# Power.net
KiCad netlist of a schematic drawn in Altium Designer
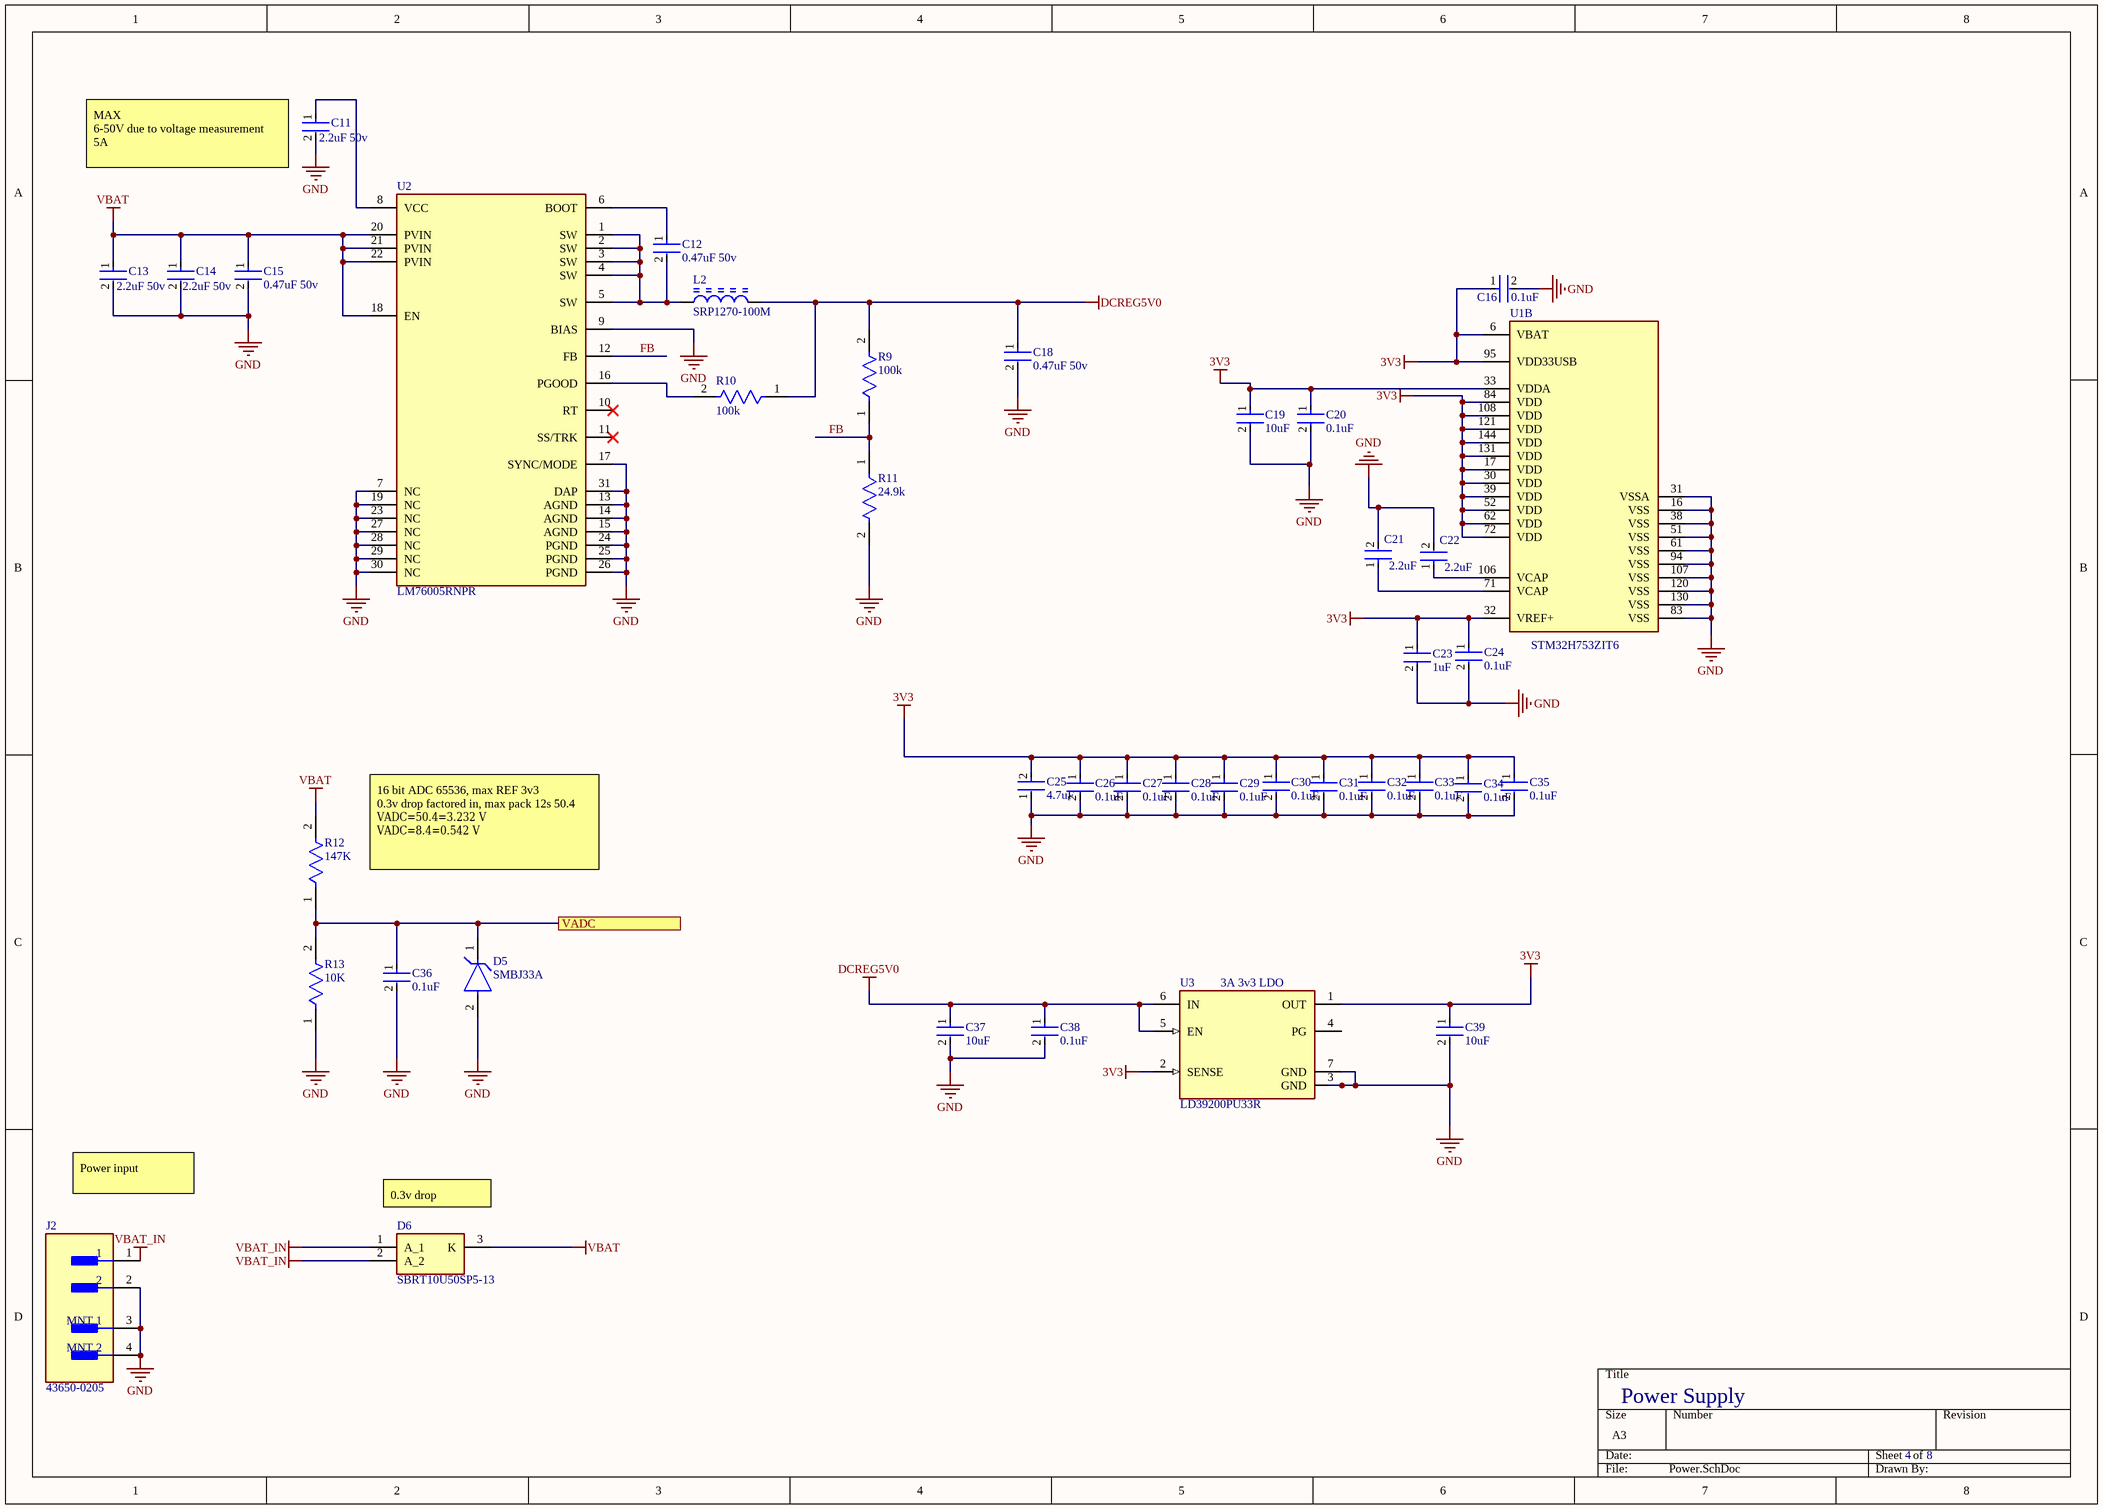
[diagram p0:  Power.SchDoc]

(export (version "E")
  (design (tool "Eeschema 10.0.6"))
  (components
    (comp (ref "C11")
      (value "2.2uF 50v")
      (footprint "FP-GRM188-0_2-IPC_C")
      (libsource (lib "Altium Content Vault") (part "11868f565c42a9108669ba33697ecf6"))
    )
    (comp (ref "C12")
      (value "0.47uF 50v")
      (footprint "FP-0603-L_1_6_0_15-W_0_8-MFG")
      (description "UMK107ABJ474KA-T")
      (fields (field (name "TOLERANCE") "10%") (field (name "VOLTAGE") "50V"))
      (libsource (lib "Altium Content Vault") (part "11868f565c42a9108669ba33697ecf6"))
    )
    (comp (ref "C13")
      (value "2.2uF 50v")
      (footprint "FP-GRM188-0_2-IPC_C")
      (libsource (lib "Altium Content Vault") (part "11868f565c42a9108669ba33697ecf6"))
    )
    (comp (ref "C14")
      (value "2.2uF 50v")
      (footprint "FP-GRM188-0_2-IPC_C")
      (libsource (lib "Altium Content Vault") (part "11868f565c42a9108669ba33697ecf6"))
    )
    (comp (ref "C15")
      (value "0.47uF 50v")
      (footprint "FP-0603-L_1_6_0_15-W_0_8-MFG")
      (description "UMK107ABJ474KA-T")
      (fields (field (name "TOLERANCE") "10%") (field (name "VOLTAGE") "50V"))
      (libsource (lib "Altium Content Vault") (part "11868f565c42a9108669ba33697ecf6"))
    )
    (comp (ref "C16")
      (value "0.1uF")
      (footprint "FP-CL10-IPC_C")
      (description "Cap Ceramic 100nF 16V X7R ±10% Pad SMD 0603 +125°C T/R\r\nCL10B104KO8WPNC")
      (fields (field (name "TOLERANCE") "10%"))
      (libsource (lib "Altium Content Vault") (part "b4654b650e69147ec39a6b967a45e02"))
    )
    (comp (ref "C18")
      (value "0.47uF 50v")
      (footprint "FP-0603-L_1_6_0_15-W_0_8-MFG")
      (description "UMK107ABJ474KA-T")
      (fields (field (name "TOLERANCE") "10%") (field (name "VOLTAGE") "50V"))
      (libsource (lib "Altium Content Vault") (part "11868f565c42a9108669ba33697ecf6"))
    )
    (comp (ref "C19")
      (value "10uF")
      (footprint "FP-CL10-IPC_C")
      (description "Cap Ceramic 10uF 16V X6S ±20% Pad SMD 0603 +105°C T/R\r\nCL10X106MO8NRNC")
      (fields (field (name "TOLERANCE") "20%"))
      (libsource (lib "Altium Content Vault") (part "b4654b650e69147ec39a6b967a45e02"))
    )
    (comp (ref "C20")
      (value "0.1uF")
      (footprint "FP-CL10-IPC_C")
      (description "Cap Ceramic 100nF 16V X7R ±10% Pad SMD 0603 +125°C T/R\r\nCL10B104KO8WPNC")
      (fields (field (name "TOLERANCE") "10%"))
      (libsource (lib "Altium Content Vault") (part "b4654b650e69147ec39a6b967a45e02"))
    )
    (comp (ref "C21")
      (value "2.2uF")
      (footprint "FP-CL10-IPC_C")
      (description "Cap Ceramic 2.2uF 16V X5R ±10% Pad SMD 0603 +85°C T/R\r\nCL10A225KO8NNND")
      (fields (field (name "TOLERANCE") "10%"))
      (libsource (lib "Altium Content Vault") (part "b4654b650e69147ec39a6b967a45e02"))
    )
    (comp (ref "C22")
      (value "2.2uF")
      (footprint "FP-CL10-IPC_C")
      (description "Cap Ceramic 2.2uF 16V X5R ±10% Pad SMD 0603 +85°C T/R\r\nCL10A225KO8NNND")
      (fields (field (name "TOLERANCE") "10%"))
      (libsource (lib "Altium Content Vault") (part "b4654b650e69147ec39a6b967a45e02"))
    )
    (comp (ref "C23")
      (value "1uF")
      (footprint "FP-CL10-IPC_C")
      (description "Cap Ceramic 1uF 16V X7R ±10% Pad SMD 0603 +125°C T/R\r\nCL10B105KO8NNNL")
      (fields (field (name "TOLERANCE") "10%"))
      (libsource (lib "Altium Content Vault") (part "b4654b650e69147ec39a6b967a45e02"))
    )
    (comp (ref "C24")
      (value "0.1uF")
      (footprint "FP-CL10-IPC_C")
      (description "Cap Ceramic 100nF 16V X7R ±10% Pad SMD 0603 +125°C T/R\r\nCL10B104KO8WPNC")
      (fields (field (name "TOLERANCE") "10%"))
      (libsource (lib "Altium Content Vault") (part "b4654b650e69147ec39a6b967a45e02"))
    )
    (comp (ref "C25")
      (value "4.7uF")
      (footprint "FP-C1608-080-0_1-MFG")
      (description "Multilayer Ceramic Capacitors 4.7μF ±10% 25V X5R SMD 0603\r\nC1608X5R1E475K080AC")
      (fields (field (name "TOLERANCE") "10%"))
      (libsource (lib "Altium Content Vault") (part "236180d848d6139a670b325ea6854c9"))
    )
    (comp (ref "C26")
      (value "0.1uF")
      (footprint "FP-CL10-IPC_C")
      (description "Cap Ceramic 100nF 16V X7R ±10% Pad SMD 0603 +125°C T/R\r\nCL10B104KO8WPNC")
      (fields (field (name "TOLERANCE") "10%"))
      (libsource (lib "Altium Content Vault") (part "b4654b650e69147ec39a6b967a45e02"))
    )
    (comp (ref "C27")
      (value "0.1uF")
      (footprint "FP-CL10-IPC_C")
      (description "Cap Ceramic 100nF 16V X7R ±10% Pad SMD 0603 +125°C T/R\r\nCL10B104KO8WPNC")
      (fields (field (name "TOLERANCE") "10%"))
      (libsource (lib "Altium Content Vault") (part "b4654b650e69147ec39a6b967a45e02"))
    )
    (comp (ref "C28")
      (value "0.1uF")
      (footprint "FP-CL10-IPC_C")
      (description "Cap Ceramic 100nF 16V X7R ±10% Pad SMD 0603 +125°C T/R\r\nCL10B104KO8WPNC")
      (fields (field (name "TOLERANCE") "10%"))
      (libsource (lib "Altium Content Vault") (part "b4654b650e69147ec39a6b967a45e02"))
    )
    (comp (ref "C29")
      (value "0.1uF")
      (footprint "FP-CL10-IPC_C")
      (description "Cap Ceramic 100nF 16V X7R ±10% Pad SMD 0603 +125°C T/R\r\nCL10B104KO8WPNC")
      (fields (field (name "TOLERANCE") "10%"))
      (libsource (lib "Altium Content Vault") (part "b4654b650e69147ec39a6b967a45e02"))
    )
    (comp (ref "C30")
      (value "0.1uF")
      (footprint "FP-CL10-IPC_C")
      (description "Cap Ceramic 100nF 16V X7R ±10% Pad SMD 0603 +125°C T/R\r\nCL10B104KO8WPNC")
      (fields (field (name "TOLERANCE") "10%"))
      (libsource (lib "Altium Content Vault") (part "b4654b650e69147ec39a6b967a45e02"))
    )
    (comp (ref "C31")
      (value "0.1uF")
      (footprint "FP-CL10-IPC_C")
      (description "Cap Ceramic 100nF 16V X7R ±10% Pad SMD 0603 +125°C T/R\r\nCL10B104KO8WPNC")
      (fields (field (name "TOLERANCE") "10%"))
      (libsource (lib "Altium Content Vault") (part "b4654b650e69147ec39a6b967a45e02"))
    )
    (comp (ref "C32")
      (value "0.1uF")
      (footprint "FP-CL10-IPC_C")
      (description "Cap Ceramic 100nF 16V X7R ±10% Pad SMD 0603 +125°C T/R\r\nCL10B104KO8WPNC")
      (fields (field (name "TOLERANCE") "10%"))
      (libsource (lib "Altium Content Vault") (part "b4654b650e69147ec39a6b967a45e02"))
    )
    (comp (ref "C33")
      (value "0.1uF")
      (footprint "FP-CL10-IPC_C")
      (description "Cap Ceramic 100nF 16V X7R ±10% Pad SMD 0603 +125°C T/R\r\nCL10B104KO8WPNC")
      (fields (field (name "TOLERANCE") "10%"))
      (libsource (lib "Altium Content Vault") (part "b4654b650e69147ec39a6b967a45e02"))
    )
    (comp (ref "C34")
      (value "0.1uF")
      (footprint "FP-CL10-IPC_C")
      (description "Cap Ceramic 100nF 16V X7R ±10% Pad SMD 0603 +125°C T/R\r\nCL10B104KO8WPNC")
      (fields (field (name "TOLERANCE") "10%"))
      (libsource (lib "Altium Content Vault") (part "b4654b650e69147ec39a6b967a45e02"))
    )
    (comp (ref "C35")
      (value "0.1uF")
      (footprint "FP-CL10-IPC_C")
      (description "Cap Ceramic 100nF 16V X7R ±10% Pad SMD 0603 +125°C T/R\r\nCL10B104KO8WPNC")
      (fields (field (name "TOLERANCE") "10%"))
      (libsource (lib "Altium Content Vault") (part "b4654b650e69147ec39a6b967a45e02"))
    )
    (comp (ref "C36")
      (value "0.1uF")
      (footprint "FP-CL10-IPC_C")
      (description "Cap Ceramic 100nF 16V X7R ±10% Pad SMD 0603 +125°C T/R\r\nCL10B104KO8WPNC")
      (fields (field (name "TOLERANCE") "10%"))
      (libsource (lib "Altium Content Vault") (part "b4654b650e69147ec39a6b967a45e02"))
    )
    (comp (ref "C37")
      (value "10uF")
      (footprint "FP-CL10-IPC_C")
      (description "Cap Ceramic 10uF 16V X6S ±20% Pad SMD 0603 +105°C T/R\r\nCL10X106MO8NRNC")
      (fields (field (name "TOLERANCE") "20%"))
      (libsource (lib "Altium Content Vault") (part "b4654b650e69147ec39a6b967a45e02"))
    )
    (comp (ref "C38")
      (value "0.1uF")
      (footprint "FP-CL10-IPC_C")
      (description "Cap Ceramic 100nF 16V X7R ±10% Pad SMD 0603 +125°C T/R\r\nCL10B104KO8WPNC")
      (fields (field (name "TOLERANCE") "10%"))
      (libsource (lib "Altium Content Vault") (part "b4654b650e69147ec39a6b967a45e02"))
    )
    (comp (ref "C39")
      (value "10uF")
      (footprint "FP-CL10-IPC_C")
      (description "Cap Ceramic 10uF 16V X6S ±20% Pad SMD 0603 +105°C T/R\r\nCL10X106MO8NRNC")
      (fields (field (name "TOLERANCE") "20%"))
      (libsource (lib "Altium Content Vault") (part "b4654b650e69147ec39a6b967a45e02"))
    )
    (comp (ref "D5")
      (value "SMBJ33A")
      (footprint "FP-SMBJ-MFG")
      (description "TVS DIODE 33V 53.3V DO214AA")
      (fields
        (field (name "MANUFACTURER") "Littelfuse Inc")
        (field (name "OCTOPART") "https://octopart.com/smbj33a-littelfuse-350829")
      )
      (libsource (lib "Altium Content Vault") (part "f813f71cba58e380607f5dd3caf9714"))
    )
    (comp (ref "D6")
      (value "SBRT10U50SP5-13")
      (footprint "SamacSys:SBRT10U50SP513")
      (description "Diode")
      (fields (field (name "MOUSER PART NUMBER") "621-SBRT10U50SP5-13"))
      (libsource (lib "*") (part "SBRT10U50SP5-13"))
    )
    (comp (ref "J2")
      (value "43650-0205")
      (footprint "FP-43650-0205-MFG")
      (description "43650-0205 Conn Wire to Board HDR 2 POS 3mm Solder RA Side Entry Thru-Hole Micro-Fit 3.0™ Tray")
      (libsource (lib "Altium Content Vault") (part "56ec3178a87b3978bdc1b3682cd516a"))
    )
    (comp (ref "L2")
      (value "SRP1270-100M")
      (footprint "BOUR-SRP1270-100M-2_V")
      (description "Shielded Power Inductor, 10 uH, +/- 20%, 10 A, -55 to 125 degC, 2-Pin SMD, RoHS, Tape and Reel")
      (fields (field (name "TOLERANCE") "±20%") (field (name "MANUFACTURER") "Bourns"))
      (libsource (lib "Altium Content Vault") (part "BOUR-IND-2A"))
    )
    (comp (ref "R9")
      (value "100k")
      (footprint "FP-RC0603-0_55-IPC_C")
      (description "RC0603FR-07100KL RES SMD 100K OHM 1% 1/10W 0603")
      (fields (field (name "TOLERANCE") "1%"))
      (libsource (lib "Altium Content Vault") (part "1029c3af85768c4190bb7ad29bc67b5"))
    )
    (comp (ref "R10")
      (value "100k")
      (footprint "FP-RC0603-0_55-IPC_C")
      (description "RC0603FR-07100KL RES SMD 100K OHM 1% 1/10W 0603")
      (fields (field (name "TOLERANCE") "1%"))
      (libsource (lib "Altium Content Vault") (part "1029c3af85768c4190bb7ad29bc67b5"))
    )
    (comp (ref "R11")
      (value "24.9k")
      (footprint "FP-RG1608-IPC_C")
      (fields (field (name "TOLERANCE") "0.1%"))
      (libsource (lib "Altium Content Vault") (part "1029c3af85768c4190bb7ad29bc67b5"))
    )
    (comp (ref "R12")
      (value "147K")
      (footprint "FP-RT0603-MFG")
      (description "RT0603BRD07147KL\r\nRES SMD 147K OHM 0.1% 1/10W 0603")
      (fields (field (name "MANUFACTURER") "Yageo") (field (name "TOLERANCE") "0.001"))
      (libsource (lib "Altium Content Vault") (part "1029c3af85768c4190bb7ad29bc67b5"))
    )
    (comp (ref "R13")
      (value "10K")
      (footprint "FP-ERJPB3-IPC_C")
      (description "ERJ-PB3B1002V\r\nRES SMD 10K OHM 0.1% 1/5W 0603")
      (fields (field (name "TOLERANCE") "0.1%"))
      (libsource (lib "Altium Content Vault") (part "1029c3af85768c4190bb7ad29bc67b5"))
    )
    (comp (ref "U1")
      (value "STM32H753ZIT6")
      (footprint "FP-LQFP144-1A-MFG")
      (description "LQFP 144 20X20X1.4 2")
      (fields
        (field (name "MANUFACTURER") "STMicroelectronics")
        (field (name "OCTOPART") "https://octopart.com/stm32h753zit6-stmicroelectronics-87879771")
      )
      (libsource (lib "Altium Content Vault") (part "eeed45f8b0ec3d8db28e558541eef73"))
    )
    (comp (ref "U2")
      (value "LM76005RNPR")
      (footprint "FP-RNP0030A-MFG")
      (description "3.5-V TO 60-V, 5-A SYNCHRONOUS S")
      (libsource (lib "Altium Content Vault") (part "e2228dfeb00daf3b479f14d7f837c1f"))
    )
    (comp (ref "U3")
      (value "LD39200PU33R")
      (footprint "FP-DFN6-7946637-MFG")
      (description "IC REG LINEAR 3.3V 2A 6DFN")
      (libsource (lib "Altium Content Vault") (part "f0cfe00d12cb984572f50007c934a2d"))
    )
  )
  (nets
    (net (code "1") (name "/FB") (class "Default")
      (node (ref "R11") (pin "1") (pinfunction "1_1") (pintype "passive"))
      (node (ref "R9") (pin "1") (pinfunction "1_1") (pintype "passive"))
      (node (ref "U2") (pin "12") (pinfunction "FB_12") (pintype "passive"))
    )
    (net (code "2") (name "/VADC") (class "Default")
      (node (ref "C36") (pin "1") (pinfunction "1_1") (pintype "passive"))
      (node (ref "D5") (pin "1") (pinfunction "C_1") (pintype "passive"))
      (node (ref "R12") (pin "1") (pinfunction "1_1") (pintype "passive"))
      (node (ref "R13") (pin "2") (pinfunction "2_2") (pintype "passive"))
    )
    (net (code "3") (name "3V3") (class "Default")
      (node (ref "C16") (pin "1") (pinfunction "1_1") (pintype "passive"))
      (node (ref "C19") (pin "1") (pinfunction "1_1") (pintype "passive"))
      (node (ref "C20") (pin "1") (pinfunction "1_1") (pintype "passive"))
      (node (ref "C23") (pin "1") (pinfunction "1_1") (pintype "passive"))
      (node (ref "C24") (pin "1") (pinfunction "1_1") (pintype "passive"))
      (node (ref "C25") (pin "2") (pinfunction "2_2") (pintype "passive"))
      (node (ref "C26") (pin "1") (pinfunction "1_1") (pintype "passive"))
      (node (ref "C27") (pin "1") (pinfunction "1_1") (pintype "passive"))
      (node (ref "C28") (pin "1") (pinfunction "1_1") (pintype "passive"))
      (node (ref "C29") (pin "1") (pinfunction "1_1") (pintype "passive"))
      (node (ref "C30") (pin "1") (pinfunction "1_1") (pintype "passive"))
      (node (ref "C31") (pin "1") (pinfunction "1_1") (pintype "passive"))
      (node (ref "C32") (pin "1") (pinfunction "1_1") (pintype "passive"))
      (node (ref "C33") (pin "1") (pinfunction "1_1") (pintype "passive"))
      (node (ref "C34") (pin "1") (pinfunction "1_1") (pintype "passive"))
      (node (ref "C35") (pin "1") (pinfunction "1_1") (pintype "passive"))
      (node (ref "C39") (pin "1") (pinfunction "1_1") (pintype "passive"))
      (node (ref "U1") (pin "108") (pinfunction "VDD_108") (pintype "power_in"))
      (node (ref "U1") (pin "121") (pinfunction "VDD_121") (pintype "power_in"))
      (node (ref "U1") (pin "131") (pinfunction "VDD_131") (pintype "power_in"))
      (node (ref "U1") (pin "144") (pinfunction "VDD_144") (pintype "power_in"))
      (node (ref "U1") (pin "17") (pinfunction "VDD_17") (pintype "power_in"))
      (node (ref "U1") (pin "30") (pinfunction "VDD_30") (pintype "power_in"))
      (node (ref "U1") (pin "32") (pinfunction "VREF+_32") (pintype "power_in"))
      (node (ref "U1") (pin "33") (pinfunction "VDDA_33") (pintype "power_in"))
      (node (ref "U1") (pin "39") (pinfunction "VDD_39") (pintype "power_in"))
      (node (ref "U1") (pin "52") (pinfunction "VDD_52") (pintype "power_in"))
      (node (ref "U1") (pin "6") (pinfunction "VBAT_6") (pintype "power_in"))
      (node (ref "U1") (pin "62") (pinfunction "VDD_62") (pintype "power_in"))
      (node (ref "U1") (pin "72") (pinfunction "VDD_72") (pintype "power_in"))
      (node (ref "U1") (pin "84") (pinfunction "VDD_84") (pintype "power_in"))
      (node (ref "U1") (pin "95") (pinfunction "VDD33USB_95") (pintype "power_in"))
      (node (ref "U3") (pin "1") (pinfunction "OUT_1") (pintype "power_in"))
      (node (ref "U3") (pin "2") (pinfunction "SENSE_2") (pintype "input"))
    )
    (net (code "4") (name "DCREG5V0") (class "Default")
      (node (ref "C18") (pin "1") (pinfunction "1_1") (pintype "passive"))
      (node (ref "C37") (pin "1") (pinfunction "1_1") (pintype "passive"))
      (node (ref "C38") (pin "1") (pinfunction "1_1") (pintype "passive"))
      (node (ref "L2") (pin "2") (pinfunction "2_2") (pintype "passive"))
      (node (ref "R10") (pin "1") (pinfunction "1_1") (pintype "passive"))
      (node (ref "R9") (pin "2") (pinfunction "2_2") (pintype "passive"))
      (node (ref "U3") (pin "5") (pinfunction "EN_5") (pintype "input"))
      (node (ref "U3") (pin "6") (pinfunction "IN_6") (pintype "power_in"))
    )
    (net (code "5") (name "GND") (class "Default")
      (node (ref "C11") (pin "2") (pinfunction "2_2") (pintype "passive"))
      (node (ref "C13") (pin "2") (pinfunction "2_2") (pintype "passive"))
      (node (ref "C14") (pin "2") (pinfunction "2_2") (pintype "passive"))
      (node (ref "C15") (pin "2") (pinfunction "2_2") (pintype "passive"))
      (node (ref "C16") (pin "2") (pinfunction "2_2") (pintype "passive"))
      (node (ref "C18") (pin "2") (pinfunction "2_2") (pintype "passive"))
      (node (ref "C19") (pin "2") (pinfunction "2_2") (pintype "passive"))
      (node (ref "C20") (pin "2") (pinfunction "2_2") (pintype "passive"))
      (node (ref "C21") (pin "2") (pinfunction "2_2") (pintype "passive"))
      (node (ref "C22") (pin "2") (pinfunction "2_2") (pintype "passive"))
      (node (ref "C23") (pin "2") (pinfunction "2_2") (pintype "passive"))
      (node (ref "C24") (pin "2") (pinfunction "2_2") (pintype "passive"))
      (node (ref "C25") (pin "1") (pinfunction "1_1") (pintype "passive"))
      (node (ref "C26") (pin "2") (pinfunction "2_2") (pintype "passive"))
      (node (ref "C27") (pin "2") (pinfunction "2_2") (pintype "passive"))
      (node (ref "C28") (pin "2") (pinfunction "2_2") (pintype "passive"))
      (node (ref "C29") (pin "2") (pinfunction "2_2") (pintype "passive"))
      (node (ref "C30") (pin "2") (pinfunction "2_2") (pintype "passive"))
      (node (ref "C31") (pin "2") (pinfunction "2_2") (pintype "passive"))
      (node (ref "C32") (pin "2") (pinfunction "2_2") (pintype "passive"))
      (node (ref "C33") (pin "2") (pinfunction "2_2") (pintype "passive"))
      (node (ref "C34") (pin "2") (pinfunction "2_2") (pintype "passive"))
      (node (ref "C35") (pin "2") (pinfunction "2_2") (pintype "passive"))
      (node (ref "C36") (pin "2") (pinfunction "2_2") (pintype "passive"))
      (node (ref "C37") (pin "2") (pinfunction "2_2") (pintype "passive"))
      (node (ref "C38") (pin "2") (pinfunction "2_2") (pintype "passive"))
      (node (ref "C39") (pin "2") (pinfunction "2_2") (pintype "passive"))
      (node (ref "D5") (pin "2") (pinfunction "A_2") (pintype "passive"))
      (node (ref "J2") (pin "2") (pinfunction "2_2") (pintype "passive"))
      (node (ref "J2") (pin "3") (pinfunction "MNT_1_3") (pintype "passive"))
      (node (ref "J2") (pin "4") (pinfunction "MNT_2_4") (pintype "passive"))
      (node (ref "R11") (pin "2") (pinfunction "2_2") (pintype "passive"))
      (node (ref "R13") (pin "1") (pinfunction "1_1") (pintype "passive"))
      (node (ref "U1") (pin "107") (pinfunction "VSS_107") (pintype "power_in"))
      (node (ref "U1") (pin "120") (pinfunction "VSS_120") (pintype "power_in"))
      (node (ref "U1") (pin "130") (pinfunction "VSS_130") (pintype "power_in"))
      (node (ref "U1") (pin "16") (pinfunction "VSS_16") (pintype "power_in"))
      (node (ref "U1") (pin "31") (pinfunction "VSSA_31") (pintype "power_in"))
      (node (ref "U1") (pin "38") (pinfunction "VSS_38") (pintype "power_in"))
      (node (ref "U1") (pin "51") (pinfunction "VSS_51") (pintype "power_in"))
      (node (ref "U1") (pin "61") (pinfunction "VSS_61") (pintype "power_in"))
      (node (ref "U1") (pin "83") (pinfunction "VSS_83") (pintype "power_in"))
      (node (ref "U1") (pin "94") (pinfunction "VSS_94") (pintype "power_in"))
      (node (ref "U2") (pin "13") (pinfunction "AGND_13") (pintype "power_in"))
      (node (ref "U2") (pin "14") (pinfunction "AGND_14") (pintype "power_in"))
      (node (ref "U2") (pin "15") (pinfunction "AGND_15") (pintype "power_in"))
      (node (ref "U2") (pin "17") (pinfunction "SYNC/MODE_17") (pintype "passive"))
      (node (ref "U2") (pin "19") (pinfunction "NC_19") (pintype "passive"))
      (node (ref "U2") (pin "23") (pinfunction "NC_23") (pintype "passive"))
      (node (ref "U2") (pin "24") (pinfunction "PGND_24") (pintype "power_in"))
      (node (ref "U2") (pin "25") (pinfunction "PGND_25") (pintype "power_in"))
      (node (ref "U2") (pin "26") (pinfunction "PGND_26") (pintype "power_in"))
      (node (ref "U2") (pin "27") (pinfunction "NC_27") (pintype "passive"))
      (node (ref "U2") (pin "28") (pinfunction "NC_28") (pintype "passive"))
      (node (ref "U2") (pin "29") (pinfunction "NC_29") (pintype "passive"))
      (node (ref "U2") (pin "30") (pinfunction "NC_30") (pintype "passive"))
      (node (ref "U2") (pin "31") (pinfunction "DAP_31") (pintype "power_in"))
      (node (ref "U2") (pin "7") (pinfunction "NC_7") (pintype "passive"))
      (node (ref "U2") (pin "9") (pinfunction "BIAS_9") (pintype "power_in"))
      (node (ref "U3") (pin "3") (pinfunction "GND_3") (pintype "power_in"))
      (node (ref "U3") (pin "7") (pinfunction "GND_7") (pintype "power_in"))
    )
    (net (code "6") (name "Net-(C12-Pad2)") (class "Default")
      (node (ref "C12") (pin "2") (pinfunction "2_2") (pintype "passive"))
      (node (ref "L2") (pin "1") (pinfunction "1_1") (pintype "passive"))
      (node (ref "U2") (pin "1") (pinfunction "SW_1") (pintype "power_in"))
      (node (ref "U2") (pin "2") (pinfunction "SW_2") (pintype "power_in"))
      (node (ref "U2") (pin "3") (pinfunction "SW_3") (pintype "power_in"))
      (node (ref "U2") (pin "4") (pinfunction "SW_4") (pintype "power_in"))
      (node (ref "U2") (pin "5") (pinfunction "SW_5") (pintype "power_in"))
    )
    (net (code "7") (name "Net-(C21-Pad1)") (class "Default")
      (node (ref "C21") (pin "1") (pinfunction "1_1") (pintype "passive"))
      (node (ref "U1") (pin "71") (pinfunction "VCAP_71") (pintype "power_in"))
    )
    (net (code "8") (name "Net-(C22-Pad1)") (class "Default")
      (node (ref "C22") (pin "1") (pinfunction "1_1") (pintype "passive"))
      (node (ref "U1") (pin "106") (pinfunction "VCAP_106") (pintype "power_in"))
    )
    (net (code "9") (name "Net-(U2-BOOT)") (class "Default")
      (node (ref "C12") (pin "1") (pinfunction "1_1") (pintype "passive"))
      (node (ref "U2") (pin "6") (pinfunction "BOOT_6") (pintype "power_in"))
    )
    (net (code "10") (name "Net-(U2-PGOOD)") (class "Default")
      (node (ref "R10") (pin "2") (pinfunction "2_2") (pintype "passive"))
      (node (ref "U2") (pin "16") (pinfunction "PGOOD_16") (pintype "open_collector"))
    )
    (net (code "11") (name "Net-(U2-VCC)") (class "Default")
      (node (ref "C11") (pin "1") (pinfunction "1_1") (pintype "passive"))
      (node (ref "U2") (pin "8") (pinfunction "VCC_8") (pintype "power_in"))
    )
    (net (code "12") (name "VBAT") (class "Default")
      (node (ref "C13") (pin "1") (pinfunction "1_1") (pintype "passive"))
      (node (ref "C14") (pin "1") (pinfunction "1_1") (pintype "passive"))
      (node (ref "C15") (pin "1") (pinfunction "1_1") (pintype "passive"))
      (node (ref "D6") (pin "3") (pinfunction "K_3") (pintype "passive"))
      (node (ref "R12") (pin "2") (pinfunction "2_2") (pintype "passive"))
      (node (ref "U2") (pin "18") (pinfunction "EN_18") (pintype "passive"))
      (node (ref "U2") (pin "20") (pinfunction "PVIN_20") (pintype "power_in"))
      (node (ref "U2") (pin "21") (pinfunction "PVIN_21") (pintype "power_in"))
      (node (ref "U2") (pin "22") (pinfunction "PVIN_22") (pintype "power_in"))
    )
    (net (code "13") (name "VBAT_IN") (class "Default")
      (node (ref "D6") (pin "1") (pinfunction "A_1_1") (pintype "passive"))
      (node (ref "D6") (pin "2") (pinfunction "A_2_2") (pintype "passive"))
      (node (ref "J2") (pin "1") (pinfunction "1_1") (pintype "passive"))
    )
    (net (code "14") (name "unconnected-(U2-RT-Pad10)") (class "Default")
      (node (ref "U2") (pin "10") (pinfunction "RT_10") (pintype "passive+no_connect"))
    )
    (net (code "15") (name "unconnected-(U2-SS{slash}TRK-Pad11)") (class "Default")
      (node (ref "U2") (pin "11") (pinfunction "SS/TRK_11") (pintype "passive+no_connect"))
    )
    (net (code "16") (name "unconnected-(U3-PG-Pad4)") (class "Default")
      (node (ref "U3") (pin "4") (pinfunction "PG_4") (pintype "open_collector"))
    )
  )
)
